# Router40_v1.net
KiCad netlist of a schematic drawn in EAGLE
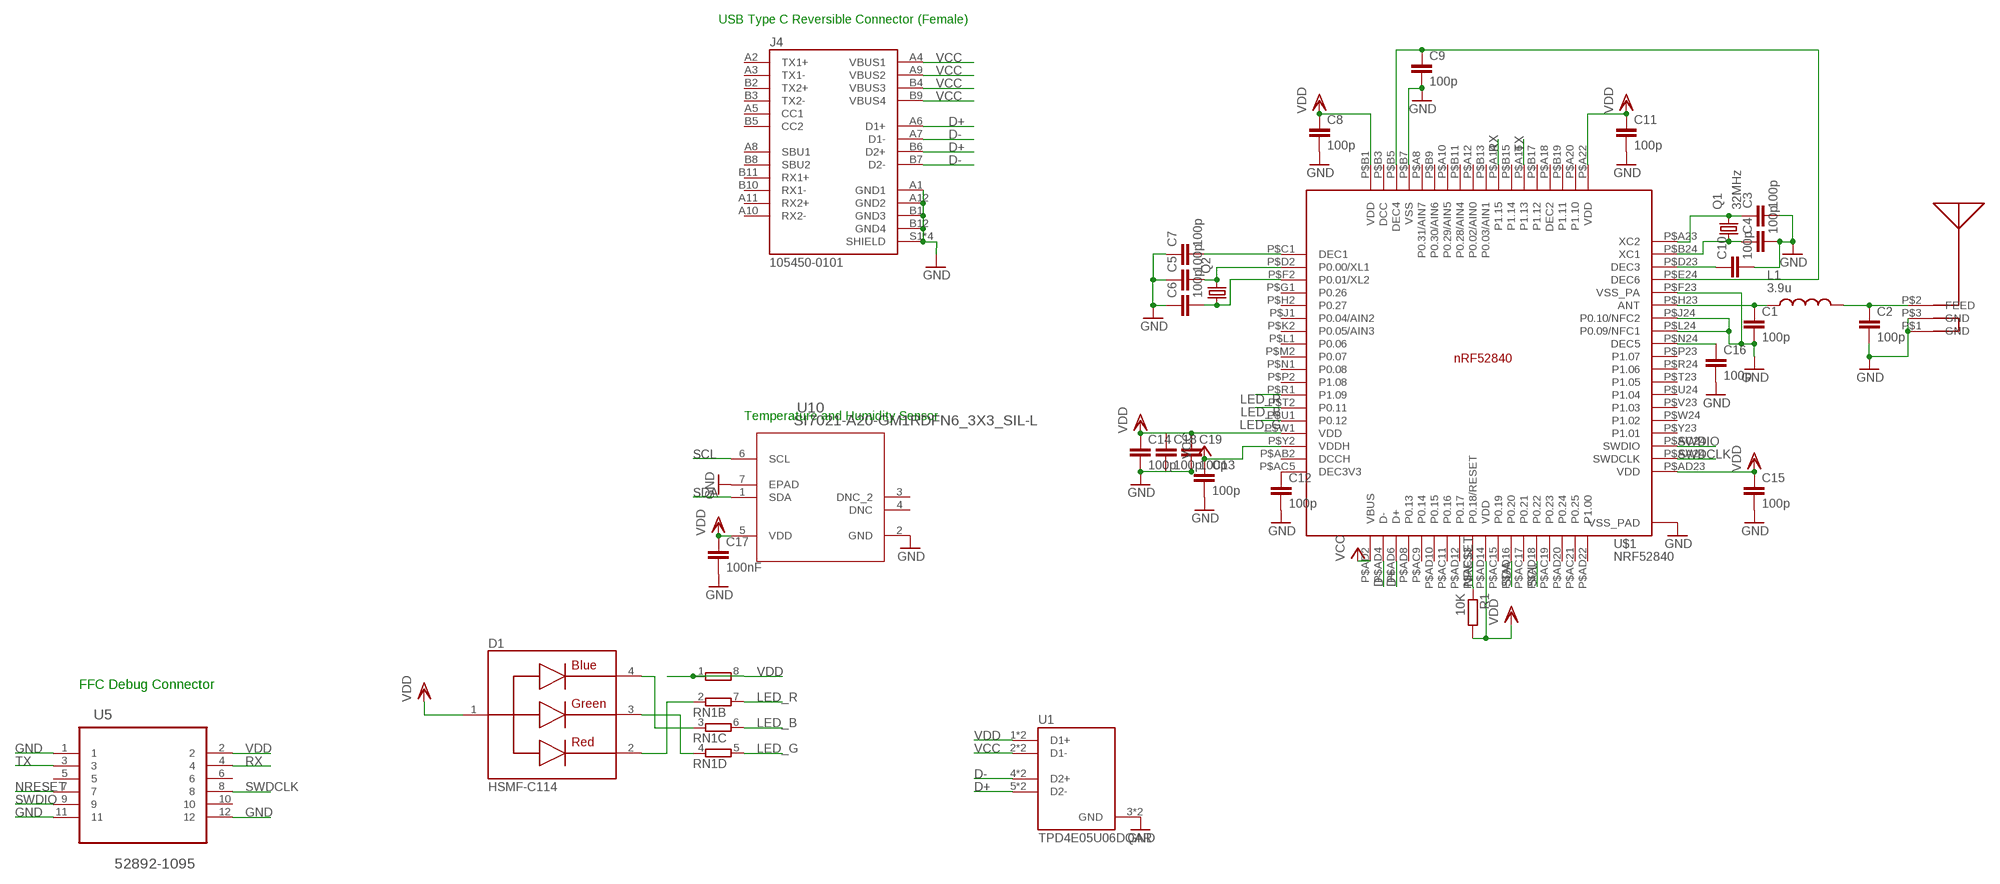
[diagram p0: schematic, sheet 1]

(export (version "E")
  (design (tool "Eeschema 10.0.6"))
  (components
    (comp (ref "C1")
      (value "100p")
      (footprint "eagle-import:C0402")
      (libsource (lib "eagle-import") (part "CC0402"))
    )
    (comp (ref "C2")
      (value "100p")
      (footprint "eagle-import:C0402")
      (libsource (lib "eagle-import") (part "CC0402"))
    )
    (comp (ref "C3")
      (value "100p")
      (footprint "eagle-import:C0402")
      (libsource (lib "eagle-import") (part "CC0402"))
    )
    (comp (ref "C4")
      (value "100p")
      (footprint "eagle-import:C0402")
      (libsource (lib "eagle-import") (part "CC0402"))
    )
    (comp (ref "C5")
      (value "100p")
      (footprint "eagle-import:C0402")
      (libsource (lib "eagle-import") (part "CC0402"))
    )
    (comp (ref "C6")
      (value "100p")
      (footprint "eagle-import:C0402")
      (libsource (lib "eagle-import") (part "CC0402"))
    )
    (comp (ref "C7")
      (value "100p")
      (footprint "eagle-import:C0402")
      (libsource (lib "eagle-import") (part "CC0402"))
    )
    (comp (ref "C8")
      (value "100p")
      (footprint "eagle-import:C0402")
      (libsource (lib "eagle-import") (part "CC0402"))
    )
    (comp (ref "C9")
      (value "100p")
      (footprint "eagle-import:C0402")
      (libsource (lib "eagle-import") (part "CC0402"))
    )
    (comp (ref "C10")
      (value "100p")
      (footprint "eagle-import:C0402")
      (libsource (lib "eagle-import") (part "CC0402"))
    )
    (comp (ref "C11")
      (value "100p")
      (footprint "eagle-import:C0402")
      (libsource (lib "eagle-import") (part "CC0402"))
    )
    (comp (ref "C12")
      (value "100p")
      (footprint "eagle-import:C0402")
      (libsource (lib "eagle-import") (part "CC0402"))
    )
    (comp (ref "C13")
      (value "100p")
      (footprint "eagle-import:C0402")
      (libsource (lib "eagle-import") (part "CC0402"))
    )
    (comp (ref "C14")
      (value "100p")
      (footprint "eagle-import:C0402")
      (libsource (lib "eagle-import") (part "CC0402"))
    )
    (comp (ref "C15")
      (value "100p")
      (footprint "eagle-import:C0402")
      (libsource (lib "eagle-import") (part "CC0402"))
    )
    (comp (ref "C16")
      (value "100p")
      (footprint "eagle-import:C0402")
      (libsource (lib "eagle-import") (part "CC0402"))
    )
    (comp (ref "C17")
      (value "100nF")
      (footprint "eagle-import:C0402")
      (libsource (lib "eagle-import") (part "CC0402"))
    )
    (comp (ref "C18")
      (value "100p")
      (footprint "eagle-import:C0402")
      (libsource (lib "eagle-import") (part "CC0402"))
    )
    (comp (ref "C19")
      (value "100p")
      (footprint "eagle-import:C0402")
      (libsource (lib "eagle-import") (part "CC0402"))
    )
    (comp (ref "D1")
      (value "HSMF-C114")
      (footprint "eagle-import:DIOSC160X150X35-4N")
      (fields (field (name "MF") "Broadcom Limited"))
      (libsource (lib "eagle-import") (part "HSMF-C114"))
    )
    (comp (ref "J4")
      (value "105450-0101")
      (footprint "eagle-import:MOLEX_105450-0101")
      (fields (field (name "MF") "Molex") (field (name "MP") "1054500101"))
      (libsource (lib "eagle-import") (part "105450-0101"))
    )
    (comp (ref "L1")
      (value "3.9u")
      (footprint "eagle-import:INDC0402X26N")
      (fields (field (name "MF") "TDK") (field (name "MP") "MHQ0402P7N5JT000"))
      (libsource (lib "eagle-import") (part "MHQ0402P7N5JT000"))
    )
    (comp (ref "Q1")
      (value "32MHz")
      (footprint "eagle-import:2.0X1.6_KX-5")
      (libsource (lib "eagle-import") (part "KX-5"))
    )
    (comp (ref "Q2")
      (value "KX-327-RT")
      (footprint "eagle-import:2.0X1.2")
      (libsource (lib "eagle-import") (part "KX-327-RT"))
    )
    (comp (ref "R1")
      (value "10K")
      (footprint "eagle-import:R0402")
      (libsource (lib "eagle-import") (part "RR0402"))
    )
    (comp (ref "RN1")
      (value "4R-N0402ARV341")
      (footprint "eagle-import:4X0402ARV341")
      (libsource (lib "eagle-import") (part "4R-N0402ARV341"))
    )
    (comp (ref "U$1")
      (value "NRF52840")
      (footprint "eagle-import:AQFN50P700X700X85_HS-74N")
      (libsource (lib "eagle-import") (part "NRF52840"))
    )
    (comp (ref "U$4")
      (value "CHIPANTENNAL2")
      (footprint "eagle-import:CHIPANTENNAL2")
      (libsource (lib "eagle-import") (part "CHIPANTENNAL2"))
    )
    (comp (ref "U1")
      (value "TPD4E05U06DQAR")
      (footprint "eagle-import:TI_TPD4E05U06DQAR")
      (fields (field (name "MF") "Texas Instruments"))
      (libsource (lib "eagle-import") (part "TPD4E05U06DQAR"))
    )
    (comp (ref "U5")
      (value "52892-1095")
      (footprint "eagle-import:MOLEX_52892-1095")
      (fields (field (name "MF") "Molex"))
      (libsource (lib "eagle-import") (part "52892-1095"))
    )
    (comp (ref "U10")
      (value "SI7021-A20-GM1RDFN6_3X3_SIL-L")
      (footprint "eagle-import:DFN6_3X3_SIL-L")
      (fields
        (field (name "MANUFACTURER_PART_NUMBER") "SI7021-A20-GM1R")
        (field (name "COPYRIGHT") "Copyright (C) 2018 Accelerated Designs. All rights reserved")
      )
      (libsource (lib "eagle-import") (part "SI7021-A20-GM1RDFN6_3X3_SIL-L"))
    )
  )
  (nets
    (net (code "1") (name "/D+") (class "Default")
      (node (ref "J4") (pin "A6") (pinfunction "D1+_A6") (pintype "passive"))
      (node (ref "J4") (pin "B6") (pinfunction "D2+_B6") (pintype "passive"))
      (node (ref "U$1") (pin "P$AD6") (pinfunction "D+_P$AD6") (pintype "bidirectional"))
      (node (ref "U1") (pin "5") (pinfunction "D2-_5") (pintype "bidirectional"))
      (node (ref "U1") (pin "6") (pinfunction "D2-_6") (pintype "bidirectional"))
    )
    (net (code "2") (name "/D-") (class "Default")
      (node (ref "J4") (pin "A7") (pinfunction "D1-_A7") (pintype "passive"))
      (node (ref "J4") (pin "B7") (pinfunction "D2-_B7") (pintype "passive"))
      (node (ref "U$1") (pin "P$AD4") (pinfunction "D-_P$AD4") (pintype "bidirectional"))
      (node (ref "U1") (pin "4") (pinfunction "D2+_4") (pintype "bidirectional"))
      (node (ref "U1") (pin "7") (pinfunction "D2+_7") (pintype "bidirectional"))
    )
    (net (code "3") (name "/LED_B") (class "Default")
      (node (ref "RN1") (pin "6") (pinfunction "2_6") (pintype "passive"))
      (node (ref "U$1") (pin "P$T2") (pinfunction "P0.11_P$T2") (pintype "bidirectional"))
    )
    (net (code "4") (name "/LED_G") (class "Default")
      (node (ref "RN1") (pin "5") (pinfunction "2_5") (pintype "passive"))
      (node (ref "U$1") (pin "P$U1") (pinfunction "P0.12_P$U1") (pintype "bidirectional"))
    )
    (net (code "5") (name "/LED_R") (class "Default")
      (node (ref "RN1") (pin "7") (pinfunction "2_7") (pintype "passive"))
      (node (ref "U$1") (pin "P$R1") (pinfunction "P1.09_P$R1") (pintype "bidirectional"))
    )
    (net (code "6") (name "/NRESET") (class "Default")
      (node (ref "R1") (pin "1") (pinfunction "1_1") (pintype "passive"))
      (node (ref "U$1") (pin "P$AC13") (pinfunction "P0.18/RESET_P$AC13") (pintype "bidirectional"))
      (node (ref "U5") (pin "7") (pinfunction "7_7") (pintype "passive"))
    )
    (net (code "7") (name "/RX") (class "Default")
      (node (ref "U$1") (pin "P$A14") (pinfunction "P1.15_P$A14") (pintype "bidirectional"))
      (node (ref "U5") (pin "4") (pinfunction "4_4") (pintype "passive"))
    )
    (net (code "8") (name "/SCL") (class "Default")
      (node (ref "U$1") (pin "P$AD18") (pinfunction "P0.22_P$AD18") (pintype "bidirectional"))
      (node (ref "U10") (pin "6") (pinfunction "SCL_6") (pintype "input"))
    )
    (net (code "9") (name "/SDA") (class "Default")
      (node (ref "U$1") (pin "P$AD16") (pinfunction "P0.20_P$AD16") (pintype "bidirectional"))
      (node (ref "U10") (pin "1") (pinfunction "SDA_1") (pintype "bidirectional"))
    )
    (net (code "10") (name "/SWDCLK") (class "Default")
      (node (ref "U$1") (pin "P$AA24") (pinfunction "SWDCLK_P$AA24") (pintype "input"))
      (node (ref "U5") (pin "8") (pinfunction "8_8") (pintype "passive"))
    )
    (net (code "11") (name "/SWDIO") (class "Default")
      (node (ref "U$1") (pin "P$AC24") (pinfunction "SWDIO_P$AC24") (pintype "bidirectional"))
      (node (ref "U5") (pin "9") (pinfunction "9_9") (pintype "passive"))
    )
    (net (code "12") (name "/TX") (class "Default")
      (node (ref "U$1") (pin "P$A16") (pinfunction "P1.13_P$A16") (pintype "bidirectional"))
      (node (ref "U5") (pin "3") (pinfunction "3_3") (pintype "passive"))
    )
    (net (code "13") (name "GND") (class "Default")
      (node (ref "C1") (pin "2") (pinfunction "2_2") (pintype "passive"))
      (node (ref "C10") (pin "2") (pinfunction "2_2") (pintype "passive"))
      (node (ref "C11") (pin "2") (pinfunction "2_2") (pintype "passive"))
      (node (ref "C12") (pin "2") (pinfunction "2_2") (pintype "passive"))
      (node (ref "C13") (pin "2") (pinfunction "2_2") (pintype "passive"))
      (node (ref "C14") (pin "2") (pinfunction "2_2") (pintype "passive"))
      (node (ref "C15") (pin "2") (pinfunction "2_2") (pintype "passive"))
      (node (ref "C16") (pin "2") (pinfunction "2_2") (pintype "passive"))
      (node (ref "C17") (pin "2") (pinfunction "2_2") (pintype "passive"))
      (node (ref "C18") (pin "2") (pinfunction "2_2") (pintype "passive"))
      (node (ref "C19") (pin "2") (pinfunction "2_2") (pintype "passive"))
      (node (ref "C2") (pin "2") (pinfunction "2_2") (pintype "passive"))
      (node (ref "C3") (pin "2") (pinfunction "2_2") (pintype "passive"))
      (node (ref "C4") (pin "2") (pinfunction "2_2") (pintype "passive"))
      (node (ref "C5") (pin "1") (pinfunction "1_1") (pintype "passive"))
      (node (ref "C6") (pin "1") (pinfunction "1_1") (pintype "passive"))
      (node (ref "C7") (pin "1") (pinfunction "1_1") (pintype "passive"))
      (node (ref "C8") (pin "2") (pinfunction "2_2") (pintype "passive"))
      (node (ref "C9") (pin "2") (pinfunction "2_2") (pintype "passive"))
      (node (ref "J4") (pin "A1") (pinfunction "GND1_A1") (pintype "passive"))
      (node (ref "J4") (pin "A12") (pinfunction "GND2_A12") (pintype "passive"))
      (node (ref "J4") (pin "B1") (pinfunction "GND3_B1") (pintype "passive"))
      (node (ref "J4") (pin "B12") (pinfunction "GND4_B12") (pintype "passive"))
      (node (ref "J4") (pin "S1") (pinfunction "SHIELD_S1") (pintype "passive"))
      (node (ref "J4") (pin "S2") (pinfunction "SHIELD_S2") (pintype "passive"))
      (node (ref "J4") (pin "S3") (pinfunction "SHIELD_S3") (pintype "passive"))
      (node (ref "J4") (pin "S4") (pinfunction "SHIELD_S4") (pintype "passive"))
      (node (ref "U$1") (pin "P$74") (pinfunction "VSS_PAD_P$74") (pintype "bidirectional"))
      (node (ref "U$1") (pin "P$75") (pinfunction "VSS_PAD_P$75") (pintype "bidirectional"))
      (node (ref "U$1") (pin "P$76") (pinfunction "VSS_PAD_P$76") (pintype "bidirectional"))
      (node (ref "U$1") (pin "P$77") (pinfunction "VSS_PAD_P$77") (pintype "bidirectional"))
      (node (ref "U$1") (pin "P$78") (pinfunction "VSS_PAD_P$78") (pintype "bidirectional"))
      (node (ref "U$1") (pin "P$79") (pinfunction "VSS_PAD_P$79") (pintype "bidirectional"))
      (node (ref "U$1") (pin "P$80") (pinfunction "VSS_PAD_P$80") (pintype "bidirectional"))
      (node (ref "U$1") (pin "P$81") (pinfunction "VSS_PAD_P$81") (pintype "bidirectional"))
      (node (ref "U$1") (pin "P$82") (pinfunction "VSS_PAD_P$82") (pintype "bidirectional"))
      (node (ref "U$1") (pin "P$83") (pinfunction "VSS_PAD_P$83") (pintype "bidirectional"))
      (node (ref "U$1") (pin "P$84") (pinfunction "VSS_PAD_P$84") (pintype "bidirectional"))
      (node (ref "U$1") (pin "P$85") (pinfunction "VSS_PAD_P$85") (pintype "bidirectional"))
      (node (ref "U$1") (pin "P$86") (pinfunction "VSS_PAD_P$86") (pintype "bidirectional"))
      (node (ref "U$1") (pin "P$87") (pinfunction "VSS_PAD_P$87") (pintype "bidirectional"))
      (node (ref "U$1") (pin "P$88") (pinfunction "VSS_PAD_P$88") (pintype "bidirectional"))
      (node (ref "U$1") (pin "P$89") (pinfunction "VSS_PAD_P$89") (pintype "bidirectional"))
      (node (ref "U$1") (pin "P$90") (pinfunction "VSS_PAD_P$90") (pintype "bidirectional"))
      (node (ref "U$1") (pin "P$B7") (pinfunction "VSS_P$B7") (pintype "power_in"))
      (node (ref "U$1") (pin "P$F23") (pinfunction "VSS_PA_P$F23") (pintype "bidirectional"))
      (node (ref "U$1") (pin "P$J24") (pinfunction "P0.10/NFC2_P$J24") (pintype "bidirectional"))
      (node (ref "U$1") (pin "P$L24") (pinfunction "P0.09/NFC1_P$L24") (pintype "bidirectional"))
      (node (ref "U$4") (pin "P$1") (pinfunction "GND_P$1") (pintype "bidirectional"))
      (node (ref "U$4") (pin "P$3") (pinfunction "GND_P$3") (pintype "bidirectional"))
      (node (ref "U1") (pin "3") (pinfunction "GND_3") (pintype "power_in"))
      (node (ref "U1") (pin "8") (pinfunction "GND_8") (pintype "power_in"))
      (node (ref "U10") (pin "2") (pinfunction "GND_2") (pintype "power_in"))
      (node (ref "U10") (pin "7") (pinfunction "EPAD_7") (pintype "passive"))
      (node (ref "U5") (pin "1") (pinfunction "1_1") (pintype "passive"))
      (node (ref "U5") (pin "11") (pinfunction "11_11") (pintype "passive"))
      (node (ref "U5") (pin "12") (pinfunction "12_12") (pintype "passive"))
    )
    (net (code "14") (name "Net-(Q1-2)") (class "Default")
      (node (ref "C3") (pin "1") (pinfunction "1_1") (pintype "passive"))
      (node (ref "Q1") (pin "3") (pinfunction "2_3") (pintype "passive"))
      (node (ref "U$1") (pin "P$A23") (pinfunction "XC2_P$A23") (pintype "output"))
    )
    (net (code "15") (name "Net-(RN1B-1)") (class "Default")
      (node (ref "D1") (pin "2") (pinfunction "2_2") (pintype "passive"))
      (node (ref "RN1") (pin "2") (pinfunction "1_2") (pintype "passive"))
    )
    (net (code "16") (name "Net-(RN1C-1)") (class "Default")
      (node (ref "D1") (pin "4") (pinfunction "4_4") (pintype "passive"))
      (node (ref "RN1") (pin "3") (pinfunction "1_3") (pintype "passive"))
    )
    (net (code "17") (name "Net-(RN1D-1)") (class "Default")
      (node (ref "D1") (pin "3") (pinfunction "3_3") (pintype "passive"))
      (node (ref "RN1") (pin "4") (pinfunction "1_4") (pintype "passive"))
    )
    (net (code "18") (name "Net-(U$1-ANT)") (class "Default")
      (node (ref "C1") (pin "1") (pinfunction "1_1") (pintype "passive"))
      (node (ref "L1") (pin "1") (pinfunction "1_1") (pintype "passive"))
      (node (ref "U$1") (pin "P$H23") (pinfunction "ANT_P$H23") (pintype "bidirectional"))
    )
    (net (code "19") (name "Net-(U$1-DEC1)") (class "Default")
      (node (ref "C7") (pin "2") (pinfunction "2_2") (pintype "passive"))
      (node (ref "U$1") (pin "P$C1") (pinfunction "DEC1_P$C1") (pintype "power_in"))
    )
    (net (code "20") (name "Net-(U$1-DEC3)") (class "Default")
      (node (ref "C10") (pin "1") (pinfunction "1_1") (pintype "passive"))
      (node (ref "U$1") (pin "P$D23") (pinfunction "DEC3_P$D23") (pintype "bidirectional"))
    )
    (net (code "21") (name "Net-(U$1-DEC3V3)") (class "Default")
      (node (ref "C12") (pin "1") (pinfunction "1_1") (pintype "passive"))
      (node (ref "U$1") (pin "P$AC5") (pinfunction "DEC3V3_P$AC5") (pintype "bidirectional"))
    )
    (net (code "22") (name "Net-(U$1-DEC4)") (class "Default")
      (node (ref "C9") (pin "1") (pinfunction "1_1") (pintype "passive"))
      (node (ref "U$1") (pin "P$B5") (pinfunction "DEC4_P$B5") (pintype "power_in"))
      (node (ref "U$1") (pin "P$E24") (pinfunction "DEC6_P$E24") (pintype "bidirectional"))
    )
    (net (code "23") (name "Net-(U$1-DEC5)") (class "Default")
      (node (ref "C16") (pin "1") (pinfunction "1_1") (pintype "passive"))
      (node (ref "U$1") (pin "P$N24") (pinfunction "DEC5_P$N24") (pintype "bidirectional"))
    )
    (net (code "24") (name "Net-(U$1-P0.00{slash}XL1)") (class "Default")
      (node (ref "C5") (pin "2") (pinfunction "2_2") (pintype "passive"))
      (node (ref "Q2") (pin "2") (pinfunction "2_2") (pintype "passive"))
      (node (ref "U$1") (pin "P$D2") (pinfunction "P0.00/XL1_P$D2") (pintype "bidirectional"))
    )
    (net (code "25") (name "Net-(U$1-P0.01{slash}XL2)") (class "Default")
      (node (ref "C6") (pin "2") (pinfunction "2_2") (pintype "passive"))
      (node (ref "Q2") (pin "1") (pinfunction "1_1") (pintype "passive"))
      (node (ref "U$1") (pin "P$F2") (pinfunction "P0.01/XL2_P$F2") (pintype "bidirectional"))
    )
    (net (code "26") (name "Net-(U$1-XC1)") (class "Default")
      (node (ref "C4") (pin "1") (pinfunction "1_1") (pintype "passive"))
      (node (ref "Q1") (pin "1") (pinfunction "1_1") (pintype "passive"))
      (node (ref "U$1") (pin "P$B24") (pinfunction "XC1_P$B24") (pintype "input"))
    )
    (net (code "27") (name "Net-(U$4-FEED)") (class "Default")
      (node (ref "C2") (pin "1") (pinfunction "1_1") (pintype "passive"))
      (node (ref "L1") (pin "2") (pinfunction "2_2") (pintype "passive"))
      (node (ref "U$4") (pin "P$2") (pinfunction "FEED_P$2") (pintype "bidirectional"))
    )
    (net (code "28") (name "VCC") (class "Default")
      (node (ref "C13") (pin "1") (pinfunction "1_1") (pintype "passive"))
      (node (ref "J4") (pin "A4") (pinfunction "VBUS1_A4") (pintype "passive"))
      (node (ref "J4") (pin "A9") (pinfunction "VBUS2_A9") (pintype "passive"))
      (node (ref "J4") (pin "B4") (pinfunction "VBUS3_B4") (pintype "passive"))
      (node (ref "J4") (pin "B9") (pinfunction "VBUS4_B9") (pintype "passive"))
      (node (ref "U$1") (pin "P$AD2") (pinfunction "VBUS_P$AD2") (pintype "power_in"))
      (node (ref "U$1") (pin "P$Y2") (pinfunction "VDDH_P$Y2") (pintype "power_in"))
      (node (ref "U1") (pin "2") (pinfunction "D1-_2") (pintype "bidirectional"))
      (node (ref "U1") (pin "9") (pinfunction "D1-_9") (pintype "bidirectional"))
    )
    (net (code "29") (name "VDD") (class "Default")
      (node (ref "C11") (pin "1") (pinfunction "1_1") (pintype "passive"))
      (node (ref "C14") (pin "1") (pinfunction "1_1") (pintype "passive"))
      (node (ref "C15") (pin "1") (pinfunction "1_1") (pintype "passive"))
      (node (ref "C17") (pin "1") (pinfunction "1_1") (pintype "passive"))
      (node (ref "C18") (pin "1") (pinfunction "1_1") (pintype "passive"))
      (node (ref "C19") (pin "1") (pinfunction "1_1") (pintype "passive"))
      (node (ref "C8") (pin "1") (pinfunction "1_1") (pintype "passive"))
      (node (ref "D1") (pin "1") (pinfunction "1_1") (pintype "passive"))
      (node (ref "R1") (pin "2") (pinfunction "2_2") (pintype "passive"))
      (node (ref "RN1") (pin "1") (pinfunction "1_1") (pintype "passive"))
      (node (ref "RN1") (pin "8") (pinfunction "2_8") (pintype "passive"))
      (node (ref "U$1") (pin "P$A22") (pinfunction "VDD_P$A22") (pintype "power_in"))
      (node (ref "U$1") (pin "P$AD14") (pinfunction "VDD_P$AD14") (pintype "power_in"))
      (node (ref "U$1") (pin "P$AD23") (pinfunction "VDD_P$AD23") (pintype "power_in"))
      (node (ref "U$1") (pin "P$B1") (pinfunction "VDD_P$B1") (pintype "power_in"))
      (node (ref "U$1") (pin "P$W1") (pinfunction "VDD_P$W1") (pintype "power_in"))
      (node (ref "U1") (pin "1") (pinfunction "D1+_1") (pintype "bidirectional"))
      (node (ref "U1") (pin "10") (pinfunction "D1+_10") (pintype "bidirectional"))
      (node (ref "U10") (pin "5") (pinfunction "VDD_5") (pintype "power_in"))
      (node (ref "U5") (pin "2") (pinfunction "2_2") (pintype "passive"))
    )
    (net (code "30") (name "unconnected-(J4-CC1-PadA5)") (class "Default")
      (node (ref "J4") (pin "A5") (pinfunction "CC1_A5") (pintype "passive"))
    )
    (net (code "31") (name "unconnected-(J4-CC2-PadB5)") (class "Default")
      (node (ref "J4") (pin "B5") (pinfunction "CC2_B5") (pintype "passive"))
    )
    (net (code "32") (name "unconnected-(J4-RX1+-PadB11)") (class "Default")
      (node (ref "J4") (pin "B11") (pinfunction "RX1+_B11") (pintype "passive"))
    )
    (net (code "33") (name "unconnected-(J4-RX1--PadB10)") (class "Default")
      (node (ref "J4") (pin "B10") (pinfunction "RX1-_B10") (pintype "passive"))
    )
    (net (code "34") (name "unconnected-(J4-RX2+-PadA11)") (class "Default")
      (node (ref "J4") (pin "A11") (pinfunction "RX2+_A11") (pintype "passive"))
    )
    (net (code "35") (name "unconnected-(J4-RX2--PadA10)") (class "Default")
      (node (ref "J4") (pin "A10") (pinfunction "RX2-_A10") (pintype "passive"))
    )
    (net (code "36") (name "unconnected-(J4-SBU1-PadA8)") (class "Default")
      (node (ref "J4") (pin "A8") (pinfunction "SBU1_A8") (pintype "passive"))
    )
    (net (code "37") (name "unconnected-(J4-SBU2-PadB8)") (class "Default")
      (node (ref "J4") (pin "B8") (pinfunction "SBU2_B8") (pintype "passive"))
    )
    (net (code "38") (name "unconnected-(J4-TX1+-PadA2)") (class "Default")
      (node (ref "J4") (pin "A2") (pinfunction "TX1+_A2") (pintype "passive"))
    )
    (net (code "39") (name "unconnected-(J4-TX1--PadA3)") (class "Default")
      (node (ref "J4") (pin "A3") (pinfunction "TX1-_A3") (pintype "passive"))
    )
    (net (code "40") (name "unconnected-(J4-TX2+-PadB2)") (class "Default")
      (node (ref "J4") (pin "B2") (pinfunction "TX2+_B2") (pintype "passive"))
    )
    (net (code "41") (name "unconnected-(J4-TX2--PadB3)") (class "Default")
      (node (ref "J4") (pin "B3") (pinfunction "TX2-_B3") (pintype "passive"))
    )
    (net (code "42") (name "unconnected-(U$1-DCC-PadP$B3)") (class "Default")
      (node (ref "U$1") (pin "P$B3") (pinfunction "DCC_P$B3") (pintype "output"))
    )
    (net (code "43") (name "unconnected-(U$1-DCCH-PadP$AB2)") (class "Default")
      (node (ref "U$1") (pin "P$AB2") (pinfunction "DCCH_P$AB2") (pintype "bidirectional"))
    )
    (net (code "44") (name "unconnected-(U$1-DEC2-PadP$A18)") (class "Default")
      (node (ref "U$1") (pin "P$A18") (pinfunction "DEC2_P$A18") (pintype "bidirectional"))
    )
    (net (code "45") (name "unconnected-(U$1-P0.02{slash}AIN0-PadP$A12)") (class "Default")
      (node (ref "U$1") (pin "P$A12") (pinfunction "P0.02/AIN0_P$A12") (pintype "bidirectional"))
    )
    (net (code "46") (name "unconnected-(U$1-P0.03{slash}AIN1-PadP$B13)") (class "Default")
      (node (ref "U$1") (pin "P$B13") (pinfunction "P0.03/AIN1_P$B13") (pintype "bidirectional"))
    )
    (net (code "47") (name "unconnected-(U$1-P0.04{slash}AIN2-PadP$J1)") (class "Default")
      (node (ref "U$1") (pin "P$J1") (pinfunction "P0.04/AIN2_P$J1") (pintype "bidirectional"))
    )
    (net (code "48") (name "unconnected-(U$1-P0.05{slash}AIN3-PadP$K2)") (class "Default")
      (node (ref "U$1") (pin "P$K2") (pinfunction "P0.05/AIN3_P$K2") (pintype "bidirectional"))
    )
    (net (code "49") (name "unconnected-(U$1-P0.06-PadP$L1)") (class "Default")
      (node (ref "U$1") (pin "P$L1") (pinfunction "P0.06_P$L1") (pintype "bidirectional"))
    )
    (net (code "50") (name "unconnected-(U$1-P0.07-PadP$M2)") (class "Default")
      (node (ref "U$1") (pin "P$M2") (pinfunction "P0.07_P$M2") (pintype "bidirectional"))
    )
    (net (code "51") (name "unconnected-(U$1-P0.08-PadP$N1)") (class "Default")
      (node (ref "U$1") (pin "P$N1") (pinfunction "P0.08_P$N1") (pintype "bidirectional"))
    )
    (net (code "52") (name "unconnected-(U$1-P0.13-PadP$AD8)") (class "Default")
      (node (ref "U$1") (pin "P$AD8") (pinfunction "P0.13_P$AD8") (pintype "bidirectional"))
    )
    (net (code "53") (name "unconnected-(U$1-P0.14-PadP$AC9)") (class "Default")
      (node (ref "U$1") (pin "P$AC9") (pinfunction "P0.14_P$AC9") (pintype "bidirectional"))
    )
    (net (code "54") (name "unconnected-(U$1-P0.15-PadP$AD10)") (class "Default")
      (node (ref "U$1") (pin "P$AD10") (pinfunction "P0.15_P$AD10") (pintype "bidirectional"))
    )
    (net (code "55") (name "unconnected-(U$1-P0.16-PadP$AC11)") (class "Default")
      (node (ref "U$1") (pin "P$AC11") (pinfunction "P0.16_P$AC11") (pintype "bidirectional"))
    )
    (net (code "56") (name "unconnected-(U$1-P0.17-PadP$AD12)") (class "Default")
      (node (ref "U$1") (pin "P$AD12") (pinfunction "P0.17_P$AD12") (pintype "bidirectional"))
    )
    (net (code "57") (name "unconnected-(U$1-P0.19-PadP$AC15)") (class "Default")
      (node (ref "U$1") (pin "P$AC15") (pinfunction "P0.19_P$AC15") (pintype "bidirectional"))
    )
    (net (code "58") (name "unconnected-(U$1-P0.21-PadP$AC17)") (class "Default")
      (node (ref "U$1") (pin "P$AC17") (pinfunction "P0.21_P$AC17") (pintype "bidirectional"))
    )
    (net (code "59") (name "unconnected-(U$1-P0.23-PadP$AC19)") (class "Default")
      (node (ref "U$1") (pin "P$AC19") (pinfunction "P0.23_P$AC19") (pintype "bidirectional"))
    )
    (net (code "60") (name "unconnected-(U$1-P0.24-PadP$AD20)") (class "Default")
      (node (ref "U$1") (pin "P$AD20") (pinfunction "P0.24_P$AD20") (pintype "bidirectional"))
    )
    (net (code "61") (name "unconnected-(U$1-P0.25-PadP$AC21)") (class "Default")
      (node (ref "U$1") (pin "P$AC21") (pinfunction "P0.25_P$AC21") (pintype "bidirectional"))
    )
    (net (code "62") (name "unconnected-(U$1-P0.26-PadP$G1)") (class "Default")
      (node (ref "U$1") (pin "P$G1") (pinfunction "P0.26_P$G1") (pintype "bidirectional"))
    )
    (net (code "63") (name "unconnected-(U$1-P0.27-PadP$H2)") (class "Default")
      (node (ref "U$1") (pin "P$H2") (pinfunction "P0.27_P$H2") (pintype "bidirectional"))
    )
    (net (code "64") (name "unconnected-(U$1-P0.28{slash}AIN4-PadP$B11)") (class "Default")
      (node (ref "U$1") (pin "P$B11") (pinfunction "P0.28/AIN4_P$B11") (pintype "bidirectional"))
    )
    (net (code "65") (name "unconnected-(U$1-P0.29{slash}AIN5-PadP$A10)") (class "Default")
      (node (ref "U$1") (pin "P$A10") (pinfunction "P0.29/AIN5_P$A10") (pintype "bidirectional"))
    )
    (net (code "66") (name "unconnected-(U$1-P0.30{slash}AIN6-PadP$B9)") (class "Default")
      (node (ref "U$1") (pin "P$B9") (pinfunction "P0.30/AIN6_P$B9") (pintype "bidirectional"))
    )
    (net (code "67") (name "unconnected-(U$1-P0.31{slash}AIN7-PadP$A8)") (class "Default")
      (node (ref "U$1") (pin "P$A8") (pinfunction "P0.31/AIN7_P$A8") (pintype "bidirectional"))
    )
    (net (code "68") (name "unconnected-(U$1-P1.00-PadP$AD22)") (class "Default")
      (node (ref "U$1") (pin "P$AD22") (pinfunction "P1.00_P$AD22") (pintype "bidirectional"))
    )
    (net (code "69") (name "unconnected-(U$1-P1.01-PadP$Y23)") (class "Default")
      (node (ref "U$1") (pin "P$Y23") (pinfunction "P1.01_P$Y23") (pintype "bidirectional"))
    )
    (net (code "70") (name "unconnected-(U$1-P1.02-PadP$W24)") (class "Default")
      (node (ref "U$1") (pin "P$W24") (pinfunction "P1.02_P$W24") (pintype "bidirectional"))
    )
    (net (code "71") (name "unconnected-(U$1-P1.03-PadP$V23)") (class "Default")
      (node (ref "U$1") (pin "P$V23") (pinfunction "P1.03_P$V23") (pintype "bidirectional"))
    )
    (net (code "72") (name "unconnected-(U$1-P1.04-PadP$U24)") (class "Default")
      (node (ref "U$1") (pin "P$U24") (pinfunction "P1.04_P$U24") (pintype "bidirectional"))
    )
    (net (code "73") (name "unconnected-(U$1-P1.05-PadP$T23)") (class "Default")
      (node (ref "U$1") (pin "P$T23") (pinfunction "P1.05_P$T23") (pintype "bidirectional"))
    )
    (net (code "74") (name "unconnected-(U$1-P1.06-PadP$R24)") (class "Default")
      (node (ref "U$1") (pin "P$R24") (pinfunction "P1.06_P$R24") (pintype "bidirectional"))
    )
    (net (code "75") (name "unconnected-(U$1-P1.07-PadP$P23)") (class "Default")
      (node (ref "U$1") (pin "P$P23") (pinfunction "P1.07_P$P23") (pintype "bidirectional"))
    )
    (net (code "76") (name "unconnected-(U$1-P1.08-PadP$P2)") (class "Default")
      (node (ref "U$1") (pin "P$P2") (pinfunction "P1.08_P$P2") (pintype "bidirectional"))
    )
    (net (code "77") (name "unconnected-(U$1-P1.10-PadP$A20)") (class "Default")
      (node (ref "U$1") (pin "P$A20") (pinfunction "P1.10_P$A20") (pintype "bidirectional"))
    )
    (net (code "78") (name "unconnected-(U$1-P1.11-PadP$B19)") (class "Default")
      (node (ref "U$1") (pin "P$B19") (pinfunction "P1.11_P$B19") (pintype "bidirectional"))
    )
    (net (code "79") (name "unconnected-(U$1-P1.12-PadP$B17)") (class "Default")
      (node (ref "U$1") (pin "P$B17") (pinfunction "P1.12_P$B17") (pintype "bidirectional"))
    )
    (net (code "80") (name "unconnected-(U$1-P1.14-PadP$B15)") (class "Default")
      (node (ref "U$1") (pin "P$B15") (pinfunction "P1.14_P$B15") (pintype "bidirectional"))
    )
    (net (code "81") (name "unconnected-(U5-Pad5)") (class "Default")
      (node (ref "U5") (pin "5") (pinfunction "5_5") (pintype "passive"))
    )
    (net (code "82") (name "unconnected-(U5-Pad6)") (class "Default")
      (node (ref "U5") (pin "6") (pinfunction "6_6") (pintype "passive"))
    )
    (net (code "83") (name "unconnected-(U5-Pad10)") (class "Default")
      (node (ref "U5") (pin "10") (pinfunction "10_10") (pintype "passive"))
    )
    (net (code "84") (name "unconnected-(U10-DNC-Pad4)") (class "Default")
      (node (ref "U10") (pin "4") (pinfunction "DNC_4") (pintype "no_connect"))
    )
    (net (code "85") (name "unconnected-(U10-DNC_2-Pad3)") (class "Default")
      (node (ref "U10") (pin "3") (pinfunction "DNC_2_3") (pintype "no_connect"))
    )
  )
)
